# 000_POWER_MODULE.net
KiCad netlist of a schematic drawn in Altium Designer
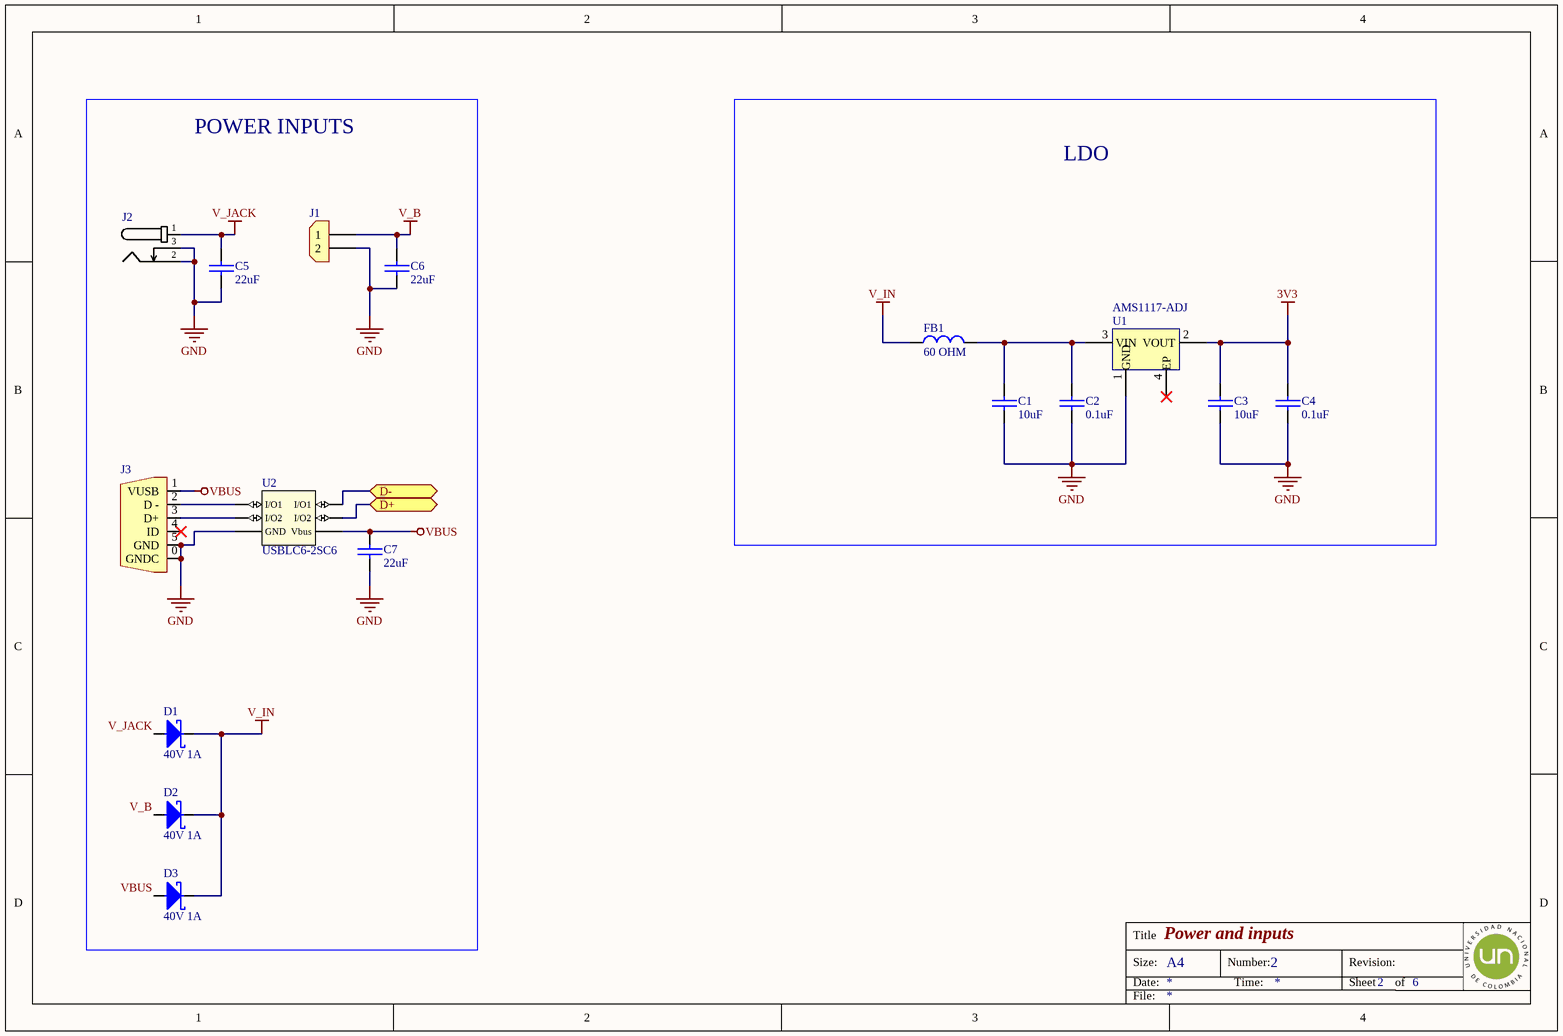
[diagram p0: 000_POWER_MODULE.SchDoc]

(export (version "E")
  (design (tool "Eeschema 10.0.6"))
  (components
    (comp (ref "C1")
      (value "10uF")
      (footprint "0603_cap")
      (description "10V 10uF X5R ±10% 0603 Multilayer Ceramic Capacitors MLCC - SMD/SMT ROHS")
      (fields
        (field (name "MANUFACTURER") "CCTC")
        (field (name "MANUFACTURER PART NUMBER") "TCC0603X5R106K100CT")
      )
      (libsource (lib "shared_lib") (part "Cap_10uF_0603_10V"))
    )
    (comp (ref "C2")
      (value "0.1uF")
      (footprint "0603_cap")
      (description "50V 100nF Y5V -20%~+80% 0603 Multilayer Ceramic Capacitors MLCC - SMD/SMT ROHS")
      (fields
        (field (name "MANUFACTURER") "Walsin Tech Corp")
        (field (name "MANUFACTURER PART NUMBER") "0603F104Z500CT")
      )
      (libsource (lib "shared_lib") (part "Cap_0.1uF_0603_50V"))
    )
    (comp (ref "C3")
      (value "10uF")
      (footprint "0603_cap")
      (description "10V 10uF X5R ±10% 0603 Multilayer Ceramic Capacitors MLCC - SMD/SMT ROHS")
      (fields
        (field (name "MANUFACTURER") "CCTC")
        (field (name "MANUFACTURER PART NUMBER") "TCC0603X5R106K100CT")
      )
      (libsource (lib "shared_lib") (part "Cap_10uF_0603_10V"))
    )
    (comp (ref "C4")
      (value "0.1uF")
      (footprint "0603_cap")
      (description "50V 100nF Y5V -20%~+80% 0603 Multilayer Ceramic Capacitors MLCC - SMD/SMT ROHS")
      (fields
        (field (name "MANUFACTURER") "Walsin Tech Corp")
        (field (name "MANUFACTURER PART NUMBER") "0603F104Z500CT")
      )
      (libsource (lib "shared_lib") (part "Cap_0.1uF_0603_50V"))
    )
    (comp (ref "C5")
      (value "22uF")
      (footprint "0603_cap")
      (description "6.3V 22uF X5R ±20% 0805 Multilayer Ceramic Capacitors MLCC - SMD/SMT ROHS")
      (fields
        (field (name "MANUFACTURER") "Samsung Electro-Mechanics")
        (field (name "MANUFACTURER PART NUMBER") "CL21A226MQQNNNE")
      )
      (libsource (lib "shared_lib") (part "Cap_22uF_0805_6V3"))
    )
    (comp (ref "C6")
      (value "22uF")
      (footprint "0603_cap")
      (description "6.3V 22uF X5R ±20% 0805 Multilayer Ceramic Capacitors MLCC - SMD/SMT ROHS")
      (fields
        (field (name "MANUFACTURER") "Samsung Electro-Mechanics")
        (field (name "MANUFACTURER PART NUMBER") "CL21A226MQQNNNE")
      )
      (libsource (lib "shared_lib") (part "Cap_22uF_0805_6V3"))
    )
    (comp (ref "C7")
      (value "22uF")
      (footprint "0603_cap")
      (description "6.3V 22uF X5R ±20% 0805 Multilayer Ceramic Capacitors MLCC - SMD/SMT ROHS")
      (fields
        (field (name "MANUFACTURER") "Samsung Electro-Mechanics")
        (field (name "MANUFACTURER PART NUMBER") "CL21A226MQQNNNE")
      )
      (libsource (lib "shared_lib") (part "Cap_22uF_0805_6V3"))
    )
    (comp (ref "D1")
      (value "40V 1A")
      (footprint "SOD_123")
      (description "DIODE SCHOTTKY 40V 1A SOD123F")
      (fields
        (field (name "MANUFACTURER") "Shanghai Prisemi Elec")
        (field (name "MANUFACTURER PART NUMBER") "PSBD1DF40V1H")
      )
      (libsource (lib "shared_lib") (part "D_Schottky_40V_1A_SOD_123F"))
    )
    (comp (ref "D2")
      (value "40V 1A")
      (footprint "SOD_123")
      (description "DIODE SCHOTTKY 40V 1A SOD123F")
      (fields
        (field (name "MANUFACTURER") "Shanghai Prisemi Elec")
        (field (name "MANUFACTURER PART NUMBER") "PSBD1DF40V1H")
      )
      (libsource (lib "shared_lib") (part "D_Schottky_40V_1A_SOD_123F"))
    )
    (comp (ref "D3")
      (value "40V 1A")
      (footprint "SOD_123")
      (description "DIODE SCHOTTKY 40V 1A SOD123F")
      (fields
        (field (name "MANUFACTURER") "Shanghai Prisemi Elec")
        (field (name "MANUFACTURER PART NUMBER") "PSBD1DF40V1H")
      )
      (libsource (lib "shared_lib") (part "D_Schottky_40V_1A_SOD_123F"))
    )
    (comp (ref "FB1")
      (value "60 OHM")
      (footprint "0603_fb")
      (description "2A 1 100mΩ 60Ω@100MHz ±25% 0603 Ferrite Beads ROHS")
      (fields
        (field (name "MANUFACTURER") "TAI-TECH")
        (field (name "MANUFACTURER PART NUMBER") "HCB1608KF-600T20")
      )
      (libsource (lib "shared_lib") (part "FB_60_0603_2A"))
    )
    (comp (ref "J1")
      (value "Connector 2pos")
      (footprint "CON_2x1_TH_5MM")
      (description "2POS 5MM")
      (fields (field (name "MANUFACTURER") "JILN") (field (name "MANUFACTURER PART NUMBER") "JL126-50002G01"))
      (libsource (lib "shared_lib") (part "Con_2x1_TH_5mm"))
    )
    (comp (ref "J2")
      (value "PWR JACK 2.1mm")
      (footprint "CON_POWER_BARREL_2.1MM_3CONN")
      (description "CONN PWR JACK 2X5.5MM SOLDER")
      (fields (field (name "MANUFACTURER") "HCTL") (field (name "MANUFACTURER PART NUMBER") "HC-DC-005-2.0T"))
      (libsource (lib "shared_lib") (part "Con_Power_Jack_2.1mm_3pins"))
    )
    (comp (ref "J3")
      (value "USB Mini B")
      (footprint "CON_5x1_SMD_miniUSB_B")
      (description "CONN RCPT USB2.0 MINI B SMD R/A")
      (fields
        (field (name "MANUFACTURER PART NUMBER") "KH-MINI-SMT-5P-Cu")
        (field (name "MANUFACTURER") "EDAC Inc.")
      )
      (libsource (lib "shared_lib") (part "Con_Mini_USB_B"))
    )
    (comp (ref "U1")
      (value "AMS1117-ADJ")
      (footprint "SOT_223")
      (fields (field (name "MANUFACTURER") "WPMtek(Wei Pan Microelectronics)"))
      (libsource (lib "shared_lib") (part "LDO_3V3_1A"))
    )
    (comp (ref "U2")
      (value "USBLC6-2SC6")
      (footprint "SOT_23_6")
      (description "TVS DIODE 5.25V 17V SOT23-6")
      (fields (field (name "MANUFACTURER") "STMicroelectronics"))
      (libsource (lib "shared_lib") (part "TVS_5.25V_2CH_SOT_23_6"))
    )
  )
  (nets
    (net (code "1") (name "/D+") (class "Default")
      (node (ref "U2") (pin "4") (pinfunction "I/O2_4") (pintype "bidirectional"))
    )
    (net (code "2") (name "/D-") (class "Default")
      (node (ref "U2") (pin "6") (pinfunction "I/O1_6") (pintype "bidirectional"))
    )
    (net (code "3") (name "3V3") (class "Default")
      (node (ref "C3") (pin "1") (pinfunction "1_1") (pintype "passive"))
      (node (ref "C4") (pin "1") (pinfunction "1_1") (pintype "passive"))
      (node (ref "U1") (pin "2") (pinfunction "VOUT_2") (pintype "passive"))
    )
    (net (code "4") (name "GND") (class "Default")
      (node (ref "C1") (pin "2") (pinfunction "2_2") (pintype "passive"))
      (node (ref "C2") (pin "2") (pinfunction "2_2") (pintype "passive"))
      (node (ref "C3") (pin "2") (pinfunction "2_2") (pintype "passive"))
      (node (ref "C4") (pin "2") (pinfunction "2_2") (pintype "passive"))
      (node (ref "C5") (pin "2") (pinfunction "2_2") (pintype "passive"))
      (node (ref "C6") (pin "2") (pinfunction "2_2") (pintype "passive"))
      (node (ref "C7") (pin "2") (pinfunction "2_2") (pintype "passive"))
      (node (ref "J1") (pin "2") (pinfunction "2_2") (pintype "passive"))
      (node (ref "J2") (pin "2") (pinfunction "2_2") (pintype "passive"))
      (node (ref "J2") (pin "3") (pinfunction "3_3") (pintype "passive"))
      (node (ref "J3") (pin "0") (pinfunction "GNDC_0") (pintype "passive"))
      (node (ref "J3") (pin "5") (pinfunction "GND_5") (pintype "passive"))
      (node (ref "U1") (pin "1") (pinfunction "GND_1") (pintype "passive"))
      (node (ref "U2") (pin "2") (pinfunction "GND_2") (pintype "power_in"))
    )
    (net (code "5") (name "Net-(J3-D+)") (class "Default")
      (node (ref "J3") (pin "3") (pinfunction "D+_3") (pintype "passive"))
      (node (ref "U2") (pin "3") (pinfunction "I/O2_3") (pintype "bidirectional"))
    )
    (net (code "6") (name "Net-(J3-D_-)") (class "Default")
      (node (ref "J3") (pin "2") (pinfunction "D_-_2") (pintype "passive"))
      (node (ref "U2") (pin "1") (pinfunction "I/O1_1") (pintype "bidirectional"))
    )
    (net (code "7") (name "Net-(U1-VIN)") (class "Default")
      (node (ref "C1") (pin "1") (pinfunction "1_1") (pintype "passive"))
      (node (ref "C2") (pin "1") (pinfunction "1_1") (pintype "passive"))
      (node (ref "FB1") (pin "2") (pinfunction "2_2") (pintype "passive"))
      (node (ref "U1") (pin "3") (pinfunction "VIN_3") (pintype "passive"))
    )
    (net (code "8") (name "VBUS") (class "Default")
      (node (ref "C7") (pin "1") (pinfunction "1_1") (pintype "passive"))
      (node (ref "D3") (pin "2") (pinfunction "2_2") (pintype "passive"))
      (node (ref "J3") (pin "1") (pinfunction "VUSB_1") (pintype "passive"))
      (node (ref "U2") (pin "5") (pinfunction "Vbus_5") (pintype "power_in"))
    )
    (net (code "9") (name "V_B") (class "Default")
      (node (ref "C6") (pin "1") (pinfunction "1_1") (pintype "passive"))
      (node (ref "D2") (pin "2") (pinfunction "2_2") (pintype "passive"))
      (node (ref "J1") (pin "1") (pinfunction "1_1") (pintype "passive"))
    )
    (net (code "10") (name "V_IN") (class "Default")
      (node (ref "D1") (pin "1") (pinfunction "1_1") (pintype "passive"))
      (node (ref "D2") (pin "1") (pinfunction "1_1") (pintype "passive"))
      (node (ref "D3") (pin "1") (pinfunction "1_1") (pintype "passive"))
      (node (ref "FB1") (pin "1") (pinfunction "1_1") (pintype "passive"))
    )
    (net (code "11") (name "V_JACK") (class "Default")
      (node (ref "C5") (pin "1") (pinfunction "1_1") (pintype "passive"))
      (node (ref "D1") (pin "2") (pinfunction "2_2") (pintype "passive"))
      (node (ref "J2") (pin "1") (pinfunction "1_1") (pintype "passive"))
    )
    (net (code "12") (name "unconnected-(J3-ID-Pad4)") (class "Default")
      (node (ref "J3") (pin "4") (pinfunction "ID_4") (pintype "passive+no_connect"))
    )
    (net (code "13") (name "unconnected-(U1-EP-Pad4)") (class "Default")
      (node (ref "U1") (pin "4") (pinfunction "EP_4") (pintype "passive+no_connect"))
    )
  )
)
